# 780-00012-P1_rev2_Sch_M2_Focus_Drive.net
KiCad netlist of a schematic drawn in Altium Designer
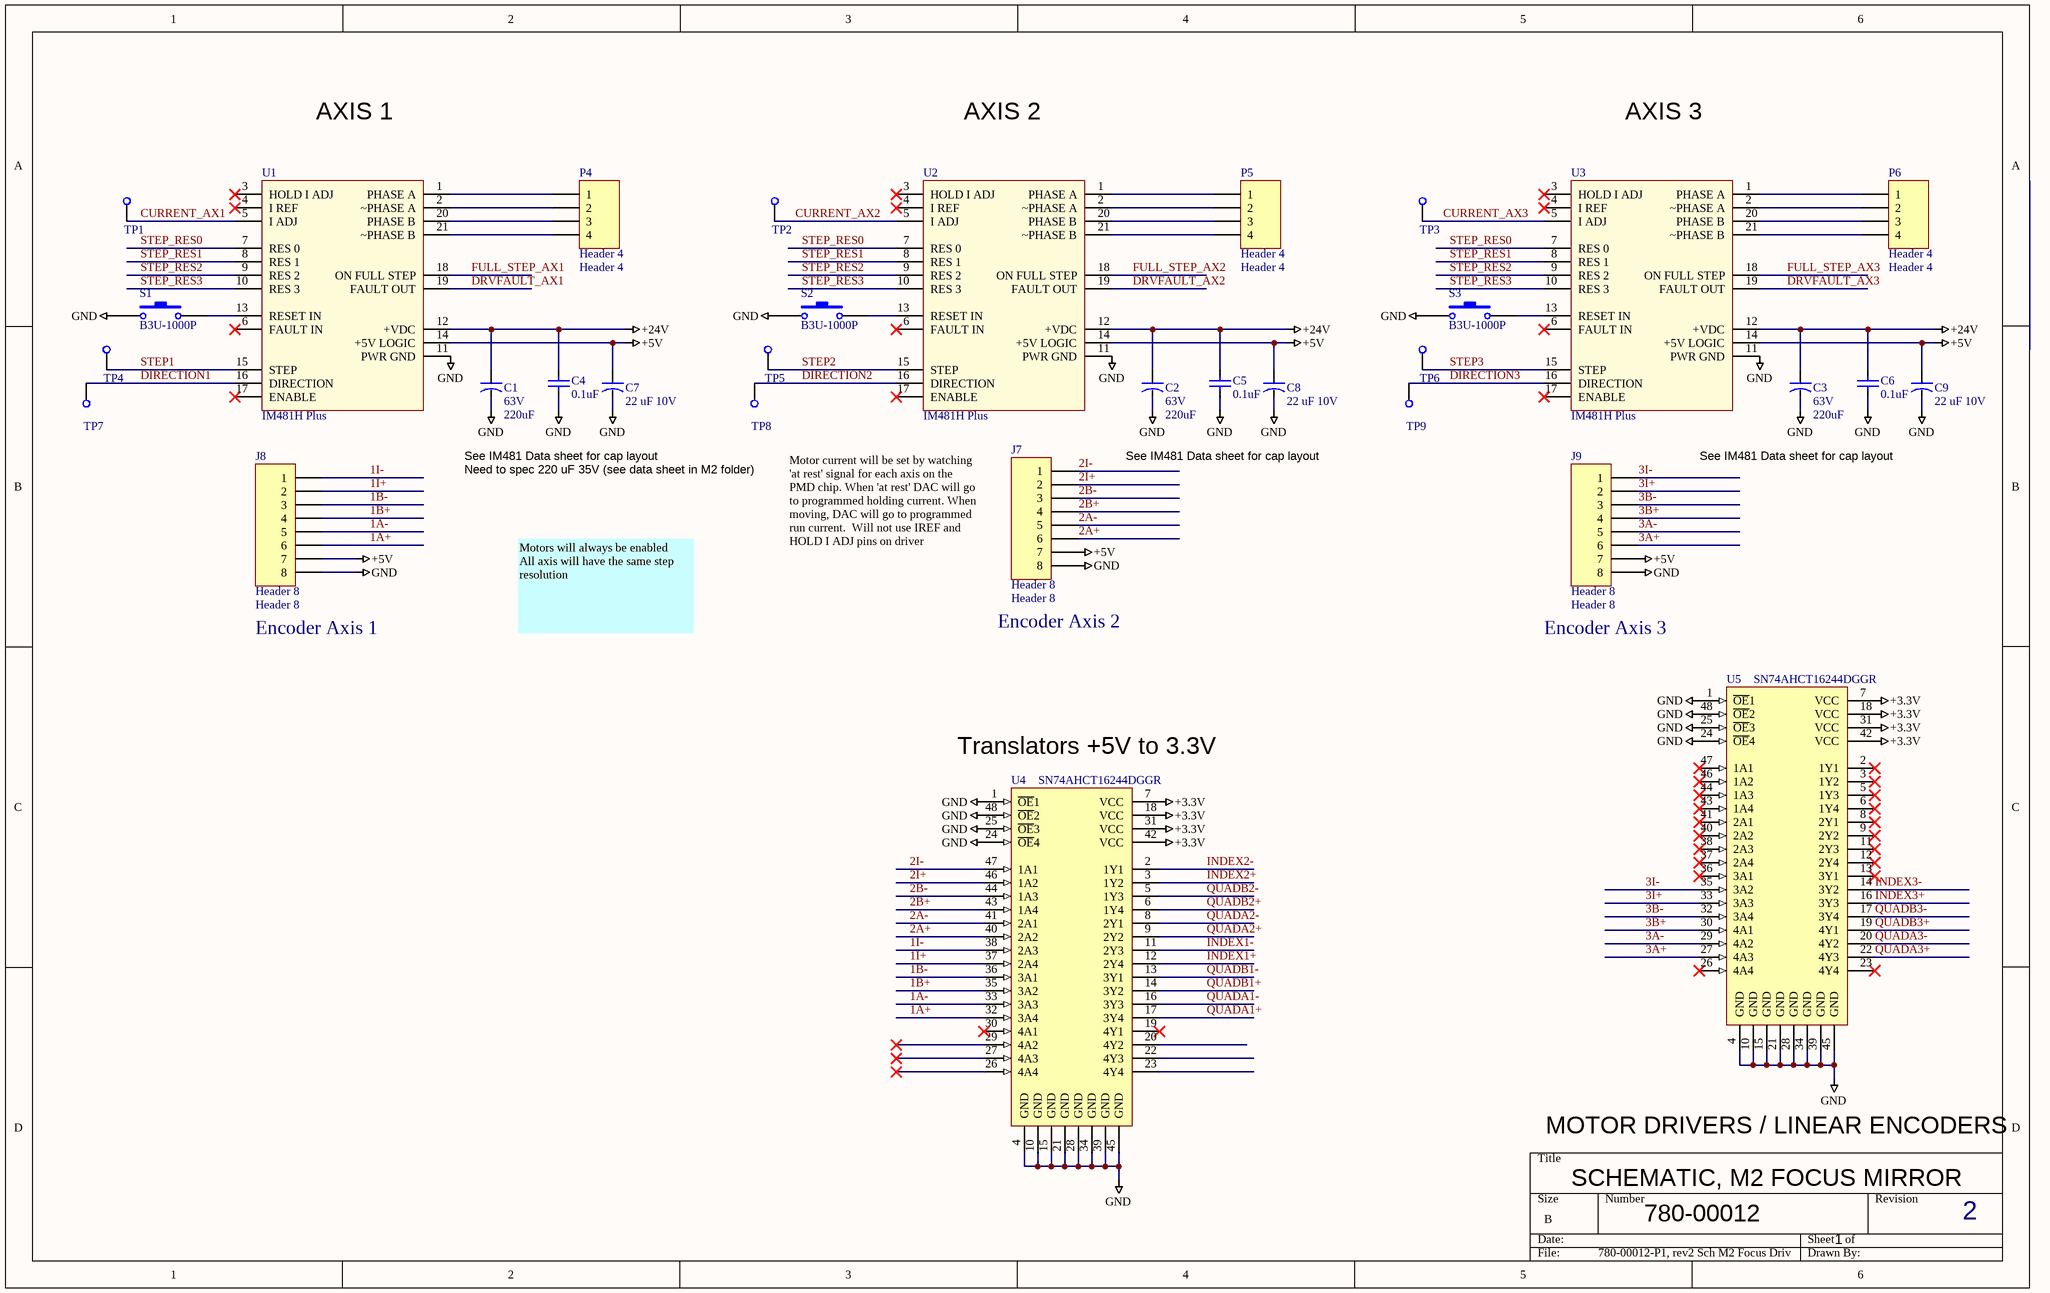
[diagram p0: 780-00012-P1, rev2 Sch M2 Focus Drive.SchDoc]

(export (version "E")
  (design (tool "Eeschema 10.0.6"))
  (components
    (comp (ref "C1")
      (value "63V")
      (footprint "CAP 220uF 63V")
      (description "CAP 220UF 63V ELECT MVH SMD")
      (fields (field (name "MANUFACTURER") "United Chemi-Con") (field (name "ALTIUM_VALUE") "220uF"))
      (libsource (lib "Richs Schematic Components") (part "Cap 220uF, 63V"))
    )
    (comp (ref "C2")
      (value "63V")
      (footprint "CAP 220uF 63V")
      (description "CAP 220UF 63V ELECT MVH SMD")
      (fields (field (name "MANUFACTURER") "United Chemi-Con") (field (name "ALTIUM_VALUE") "220uF"))
      (libsource (lib "Richs Schematic Components") (part "Cap 220uF, 63V"))
    )
    (comp (ref "C3")
      (value "63V")
      (footprint "CAP 220uF 63V")
      (description "CAP 220UF 63V ELECT MVH SMD")
      (fields (field (name "MANUFACTURER") "United Chemi-Con") (field (name "ALTIUM_VALUE") "220uF"))
      (libsource (lib "Richs Schematic Components") (part "Cap 220uF, 63V"))
    )
    (comp (ref "C4")
      (value "0.1uF")
      (footprint "SMD_0805")
      (description "Capacitor")
      (fields (field (name "Comment") "Cap SMD"))
      (libsource (lib "Richs Schematic Components") (part "Cap SMD"))
    )
    (comp (ref "C5")
      (value "0.1uF")
      (footprint "SMD_0805")
      (description "Capacitor")
      (fields (field (name "Comment") "Cap SMD"))
      (libsource (lib "Richs Schematic Components") (part "Cap SMD"))
    )
    (comp (ref "C6")
      (value "0.1uF")
      (footprint "SMD_0805")
      (description "Capacitor")
      (fields (field (name "Comment") "Cap SMD"))
      (libsource (lib "Richs Schematic Components") (part "Cap SMD"))
    )
    (comp (ref "C7")
      (value "22 uF 10V")
      (footprint "SMD_CAP_3216")
      (description "outline 3.2mm x 1.6mm")
      (fields (field (name "MANUFACTURER") "KEMET") (field (name "Comment") "16V"))
      (libsource (lib "Richs Schematic Components") (part "Cap Tant 16V"))
    )
    (comp (ref "C8")
      (value "22 uF 10V")
      (footprint "SMD_CAP_3216")
      (description "outline 3.2mm x 1.6mm")
      (fields (field (name "MANUFACTURER") "KEMET") (field (name "Comment") "16V"))
      (libsource (lib "Richs Schematic Components") (part "Cap Tant 16V"))
    )
    (comp (ref "C9")
      (value "22 uF 10V")
      (footprint "SMD_CAP_3216")
      (description "outline 3.2mm x 1.6mm")
      (fields (field (name "MANUFACTURER") "KEMET") (field (name "Comment") "16V"))
      (libsource (lib "Richs Schematic Components") (part "Cap Tant 16V"))
    )
    (comp (ref "J7")
      (value "Header 8")
      (footprint "HDR1X8 for IDC")
      (description "Header, 8-Pin")
      (fields (field (name "ALTIUM_VALUE") "Header 8"))
      (libsource (lib "Richs Schematic Components") (part "Header 8"))
    )
    (comp (ref "J8")
      (value "Header 8")
      (footprint "HDR1X8 for IDC")
      (description "Header, 8-Pin")
      (fields (field (name "ALTIUM_VALUE") "Header 8"))
      (libsource (lib "Richs Schematic Components") (part "Header 8"))
    )
    (comp (ref "J9")
      (value "Header 8")
      (footprint "HDR1X8 for IDC")
      (description "Header, 8-Pin")
      (fields (field (name "ALTIUM_VALUE") "Header 8"))
      (libsource (lib "Richs Schematic Components") (part "Header 8"))
    )
    (comp (ref "P4")
      (value "Header 4")
      (footprint "HDR1X4 for IDC")
      (description "Header, 4-Pin")
      (fields (field (name "ALTIUM_VALUE") "Header 4"))
      (libsource (lib "Richs Schematic Components") (part "Header 4"))
    )
    (comp (ref "P5")
      (value "Header 4")
      (footprint "HDR1X4 for IDC")
      (description "Header, 4-Pin")
      (fields (field (name "ALTIUM_VALUE") "Header 4"))
      (libsource (lib "Richs Schematic Components") (part "Header 4"))
    )
    (comp (ref "P6")
      (value "Header 4")
      (footprint "HDR1X4 for IDC")
      (description "Header, 4-Pin")
      (fields (field (name "ALTIUM_VALUE") "Header 4"))
      (libsource (lib "Richs Schematic Components") (part "Header 4"))
    )
    (comp (ref "S1")
      (value "B3U-1000P")
      (footprint "B3U-1000P")
      (description "Switch")
      (fields (field (name "MANUFACTURER") "Omron Electronics"))
      (libsource (lib "Miscellaneous Devices") (part "SW-PB"))
    )
    (comp (ref "S2")
      (value "B3U-1000P")
      (footprint "B3U-1000P")
      (description "Switch")
      (fields (field (name "MANUFACTURER") "Omron Electronics"))
      (libsource (lib "Miscellaneous Devices") (part "SW-PB"))
    )
    (comp (ref "S3")
      (value "B3U-1000P")
      (footprint "B3U-1000P")
      (description "Switch")
      (fields (field (name "MANUFACTURER") "Omron Electronics"))
      (libsource (lib "Miscellaneous Devices") (part "SW-PB"))
    )
    (comp (ref "TP1")
      (value "Test Point SMD")
      (footprint "SMD_TEST POINT")
      (description "SMD loop test point")
      (libsource (lib "Richs Schematic Components") (part "Test Point SMD"))
    )
    (comp (ref "TP2")
      (value "Test Point SMD")
      (footprint "SMD_TEST POINT")
      (description "SMD loop test point")
      (libsource (lib "Richs Schematic Components") (part "Test Point SMD"))
    )
    (comp (ref "TP3")
      (value "Test Point SMD")
      (footprint "SMD_TEST POINT")
      (description "SMD loop test point")
      (libsource (lib "Richs Schematic Components") (part "Test Point SMD"))
    )
    (comp (ref "TP4")
      (value "Test Point SMD")
      (footprint "SMD_TEST POINT")
      (description "SMD loop test point")
      (libsource (lib "Richs Schematic Components") (part "Test Point SMD"))
    )
    (comp (ref "TP5")
      (value "Test Point SMD")
      (footprint "SMD_TEST POINT")
      (description "SMD loop test point")
      (libsource (lib "Richs Schematic Components") (part "Test Point SMD"))
    )
    (comp (ref "TP6")
      (value "Test Point SMD")
      (footprint "SMD_TEST POINT")
      (description "SMD loop test point")
      (libsource (lib "Richs Schematic Components") (part "Test Point SMD"))
    )
    (comp (ref "TP7")
      (value "Test Point SMD")
      (footprint "SMD_TEST POINT")
      (description "SMD loop test point")
      (libsource (lib "Richs Schematic Components") (part "Test Point SMD"))
    )
    (comp (ref "TP8")
      (value "Test Point SMD")
      (footprint "SMD_TEST POINT")
      (description "SMD loop test point")
      (libsource (lib "Richs Schematic Components") (part "Test Point SMD"))
    )
    (comp (ref "TP9")
      (value "Test Point SMD")
      (footprint "SMD_TEST POINT")
      (description "SMD loop test point")
      (libsource (lib "Richs Schematic Components") (part "Test Point SMD"))
    )
    (comp (ref "U1")
      (value "IM481H Plus")
      (footprint "IM481H Vertical")
      (description "Hybrid stepper motor driver")
      (libsource (lib "Richs Schematic Components") (part "IM481H Plus"))
    )
    (comp (ref "U2")
      (value "IM481H Plus")
      (footprint "IM481H Vertical")
      (description "Hybrid stepper motor driver")
      (libsource (lib "Richs Schematic Components") (part "IM481H Plus"))
    )
    (comp (ref "U3")
      (value "IM481H Plus")
      (footprint "IM481H Vertical")
      (description "Hybrid stepper motor driver")
      (libsource (lib "Richs Schematic Components") (part "IM481H Plus"))
    )
    (comp (ref "U4")
      (value "SN74AHCT16244DGGR")
      (footprint "DGG048_N")
      (description "16-Bit Buffer/Driver with 3-State Outputs")
      (libsource (lib "TI Logic Buffer Line Driver") (part "SN74AHCT16244DGGR"))
    )
    (comp (ref "U5")
      (value "SN74AHCT16244DGGR")
      (footprint "DGG048_N")
      (description "16-Bit Buffer/Driver with 3-State Outputs")
      (libsource (lib "TI Logic Buffer Line Driver") (part "SN74AHCT16244DGGR"))
    )
  )
  (nets
    (net (code "1") (name "+3.3V") (class "Default")
      (node (ref "U4") (pin "18") (pinfunction "VCC_18") (pintype "power_in"))
      (node (ref "U4") (pin "31") (pinfunction "VCC_31") (pintype "power_in"))
      (node (ref "U4") (pin "42") (pinfunction "VCC_42") (pintype "power_in"))
      (node (ref "U4") (pin "7") (pinfunction "VCC_7") (pintype "power_in"))
      (node (ref "U5") (pin "18") (pinfunction "VCC_18") (pintype "power_in"))
      (node (ref "U5") (pin "31") (pinfunction "VCC_31") (pintype "power_in"))
      (node (ref "U5") (pin "42") (pinfunction "VCC_42") (pintype "power_in"))
      (node (ref "U5") (pin "7") (pinfunction "VCC_7") (pintype "power_in"))
    )
    (net (code "2") (name "+5V") (class "Default")
      (node (ref "C7") (pin "1") (pinfunction "1_1") (pintype "passive"))
      (node (ref "C8") (pin "1") (pinfunction "1_1") (pintype "passive"))
      (node (ref "C9") (pin "1") (pinfunction "1_1") (pintype "passive"))
      (node (ref "J7") (pin "7") (pinfunction "7_7") (pintype "passive"))
      (node (ref "J8") (pin "7") (pinfunction "7_7") (pintype "passive"))
      (node (ref "J9") (pin "7") (pinfunction "7_7") (pintype "passive"))
      (node (ref "U1") (pin "14") (pinfunction "+5V_LOGIC_14") (pintype "passive"))
      (node (ref "U2") (pin "14") (pinfunction "+5V_LOGIC_14") (pintype "passive"))
      (node (ref "U3") (pin "14") (pinfunction "+5V_LOGIC_14") (pintype "passive"))
    )
    (net (code "3") (name "+24V") (class "Default")
      (node (ref "C1") (pin "1") (pinfunction "1_1") (pintype "passive"))
      (node (ref "C2") (pin "1") (pinfunction "1_1") (pintype "passive"))
      (node (ref "C3") (pin "1") (pinfunction "1_1") (pintype "passive"))
      (node (ref "C4") (pin "2") (pinfunction "2_2") (pintype "passive"))
      (node (ref "C5") (pin "2") (pinfunction "2_2") (pintype "passive"))
      (node (ref "C6") (pin "2") (pinfunction "2_2") (pintype "passive"))
      (node (ref "U1") (pin "12") (pinfunction "+VDC_12") (pintype "passive"))
      (node (ref "U2") (pin "12") (pinfunction "+VDC_12") (pintype "passive"))
      (node (ref "U3") (pin "12") (pinfunction "+VDC_12") (pintype "passive"))
    )
    (net (code "4") (name "/1A+") (class "Default")
      (node (ref "J8") (pin "6") (pinfunction "6_6") (pintype "passive"))
      (node (ref "U4") (pin "32") (pinfunction "3A4_32") (pintype "input"))
    )
    (net (code "5") (name "/1A-") (class "Default")
      (node (ref "J8") (pin "5") (pinfunction "5_5") (pintype "passive"))
      (node (ref "U4") (pin "33") (pinfunction "3A3_33") (pintype "input"))
    )
    (net (code "6") (name "/1B+") (class "Default")
      (node (ref "J8") (pin "4") (pinfunction "4_4") (pintype "passive"))
      (node (ref "U4") (pin "35") (pinfunction "3A2_35") (pintype "input"))
    )
    (net (code "7") (name "/1B-") (class "Default")
      (node (ref "J8") (pin "3") (pinfunction "3_3") (pintype "passive"))
      (node (ref "U4") (pin "36") (pinfunction "3A1_36") (pintype "input"))
    )
    (net (code "8") (name "/1I+") (class "Default")
      (node (ref "J8") (pin "2") (pinfunction "2_2") (pintype "passive"))
      (node (ref "U4") (pin "37") (pinfunction "2A4_37") (pintype "input"))
    )
    (net (code "9") (name "/1I-") (class "Default")
      (node (ref "J8") (pin "1") (pinfunction "1_1") (pintype "passive"))
      (node (ref "U4") (pin "38") (pinfunction "2A3_38") (pintype "input"))
    )
    (net (code "10") (name "/2A+") (class "Default")
      (node (ref "J7") (pin "6") (pinfunction "6_6") (pintype "passive"))
      (node (ref "U4") (pin "40") (pinfunction "2A2_40") (pintype "input"))
    )
    (net (code "11") (name "/2A-") (class "Default")
      (node (ref "J7") (pin "5") (pinfunction "5_5") (pintype "passive"))
      (node (ref "U4") (pin "41") (pinfunction "2A1_41") (pintype "input"))
    )
    (net (code "12") (name "/2B+") (class "Default")
      (node (ref "J7") (pin "4") (pinfunction "4_4") (pintype "passive"))
      (node (ref "U4") (pin "43") (pinfunction "1A4_43") (pintype "input"))
    )
    (net (code "13") (name "/2B-") (class "Default")
      (node (ref "J7") (pin "3") (pinfunction "3_3") (pintype "passive"))
      (node (ref "U4") (pin "44") (pinfunction "1A3_44") (pintype "input"))
    )
    (net (code "14") (name "/2I+") (class "Default")
      (node (ref "J7") (pin "2") (pinfunction "2_2") (pintype "passive"))
      (node (ref "U4") (pin "46") (pinfunction "1A2_46") (pintype "input"))
    )
    (net (code "15") (name "/2I-") (class "Default")
      (node (ref "J7") (pin "1") (pinfunction "1_1") (pintype "passive"))
      (node (ref "U4") (pin "47") (pinfunction "1A1_47") (pintype "input"))
    )
    (net (code "16") (name "/3A+") (class "Default")
      (node (ref "J9") (pin "6") (pinfunction "6_6") (pintype "passive"))
      (node (ref "U5") (pin "27") (pinfunction "4A3_27") (pintype "input"))
    )
    (net (code "17") (name "/3A-") (class "Default")
      (node (ref "J9") (pin "5") (pinfunction "5_5") (pintype "passive"))
      (node (ref "U5") (pin "29") (pinfunction "4A2_29") (pintype "input"))
    )
    (net (code "18") (name "/3B+") (class "Default")
      (node (ref "J9") (pin "4") (pinfunction "4_4") (pintype "passive"))
      (node (ref "U5") (pin "30") (pinfunction "4A1_30") (pintype "input"))
    )
    (net (code "19") (name "/3B-") (class "Default")
      (node (ref "J9") (pin "3") (pinfunction "3_3") (pintype "passive"))
      (node (ref "U5") (pin "32") (pinfunction "3A4_32") (pintype "input"))
    )
    (net (code "20") (name "/3I+") (class "Default")
      (node (ref "J9") (pin "2") (pinfunction "2_2") (pintype "passive"))
      (node (ref "U5") (pin "33") (pinfunction "3A3_33") (pintype "input"))
    )
    (net (code "21") (name "/3I-") (class "Default")
      (node (ref "J9") (pin "1") (pinfunction "1_1") (pintype "passive"))
      (node (ref "U5") (pin "35") (pinfunction "3A2_35") (pintype "input"))
    )
    (net (code "22") (name "/CURRENT_AX1") (class "Default")
      (node (ref "TP1") (pin "1") (pinfunction "TP_1") (pintype "passive"))
      (node (ref "U1") (pin "5") (pinfunction "I_ADJ_5") (pintype "passive"))
    )
    (net (code "23") (name "/CURRENT_AX2") (class "Default")
      (node (ref "TP2") (pin "1") (pinfunction "TP_1") (pintype "passive"))
      (node (ref "U2") (pin "5") (pinfunction "I_ADJ_5") (pintype "passive"))
    )
    (net (code "24") (name "/CURRENT_AX3") (class "Default")
      (node (ref "TP3") (pin "1") (pinfunction "TP_1") (pintype "passive"))
      (node (ref "U3") (pin "5") (pinfunction "I_ADJ_5") (pintype "passive"))
    )
    (net (code "25") (name "/DIRECTION1") (class "Default")
      (node (ref "TP7") (pin "1") (pinfunction "TP_1") (pintype "passive"))
      (node (ref "U1") (pin "16") (pinfunction "DIRECTION_16") (pintype "passive"))
    )
    (net (code "26") (name "/DIRECTION2") (class "Default")
      (node (ref "TP8") (pin "1") (pinfunction "TP_1") (pintype "passive"))
      (node (ref "U2") (pin "16") (pinfunction "DIRECTION_16") (pintype "passive"))
    )
    (net (code "27") (name "/DIRECTION3") (class "Default")
      (node (ref "TP9") (pin "1") (pinfunction "TP_1") (pintype "passive"))
      (node (ref "U3") (pin "16") (pinfunction "DIRECTION_16") (pintype "passive"))
    )
    (net (code "28") (name "/DRVFAULT_AX1") (class "Default")
      (node (ref "U1") (pin "19") (pinfunction "FAULT_OUT_19") (pintype "passive"))
    )
    (net (code "29") (name "/DRVFAULT_AX2") (class "Default")
      (node (ref "U2") (pin "19") (pinfunction "FAULT_OUT_19") (pintype "passive"))
    )
    (net (code "30") (name "/DRVFAULT_AX3") (class "Default")
      (node (ref "U3") (pin "19") (pinfunction "FAULT_OUT_19") (pintype "passive"))
    )
    (net (code "31") (name "/FULL_STEP_AX1") (class "Default")
      (node (ref "U1") (pin "18") (pinfunction "ON_FULL_STEP_18") (pintype "passive"))
    )
    (net (code "32") (name "/FULL_STEP_AX2") (class "Default")
      (node (ref "U2") (pin "18") (pinfunction "ON_FULL_STEP_18") (pintype "passive"))
    )
    (net (code "33") (name "/FULL_STEP_AX3") (class "Default")
      (node (ref "U3") (pin "18") (pinfunction "ON_FULL_STEP_18") (pintype "passive"))
    )
    (net (code "34") (name "/INDEX1+") (class "Default")
      (node (ref "U4") (pin "12") (pinfunction "2Y4_12") (pintype "tri_state"))
    )
    (net (code "35") (name "/INDEX1-") (class "Default")
      (node (ref "U4") (pin "11") (pinfunction "2Y3_11") (pintype "tri_state"))
    )
    (net (code "36") (name "/INDEX2+") (class "Default")
      (node (ref "U4") (pin "3") (pinfunction "1Y2_3") (pintype "tri_state"))
    )
    (net (code "37") (name "/INDEX2-") (class "Default")
      (node (ref "U4") (pin "2") (pinfunction "1Y1_2") (pintype "tri_state"))
    )
    (net (code "38") (name "/INDEX3+") (class "Default")
      (node (ref "U5") (pin "16") (pinfunction "3Y3_16") (pintype "tri_state"))
    )
    (net (code "39") (name "/INDEX3-") (class "Default")
      (node (ref "U5") (pin "14") (pinfunction "3Y2_14") (pintype "tri_state"))
    )
    (net (code "40") (name "/QUADA1+") (class "Default")
      (node (ref "U4") (pin "17") (pinfunction "3Y4_17") (pintype "tri_state"))
    )
    (net (code "41") (name "/QUADA1-") (class "Default")
      (node (ref "U4") (pin "16") (pinfunction "3Y3_16") (pintype "tri_state"))
    )
    (net (code "42") (name "/QUADA2+") (class "Default")
      (node (ref "U4") (pin "9") (pinfunction "2Y2_9") (pintype "tri_state"))
    )
    (net (code "43") (name "/QUADA2-") (class "Default")
      (node (ref "U4") (pin "8") (pinfunction "2Y1_8") (pintype "tri_state"))
    )
    (net (code "44") (name "/QUADA3+") (class "Default")
      (node (ref "U5") (pin "22") (pinfunction "4Y3_22") (pintype "tri_state"))
    )
    (net (code "45") (name "/QUADA3-") (class "Default")
      (node (ref "U5") (pin "20") (pinfunction "4Y2_20") (pintype "tri_state"))
    )
    (net (code "46") (name "/QUADB1+") (class "Default")
      (node (ref "U4") (pin "14") (pinfunction "3Y2_14") (pintype "tri_state"))
    )
    (net (code "47") (name "/QUADB1-") (class "Default")
      (node (ref "U4") (pin "13") (pinfunction "3Y1_13") (pintype "tri_state"))
    )
    (net (code "48") (name "/QUADB2+") (class "Default")
      (node (ref "U4") (pin "6") (pinfunction "1Y4_6") (pintype "tri_state"))
    )
    (net (code "49") (name "/QUADB2-") (class "Default")
      (node (ref "U4") (pin "5") (pinfunction "1Y3_5") (pintype "tri_state"))
    )
    (net (code "50") (name "/QUADB3+") (class "Default")
      (node (ref "U5") (pin "19") (pinfunction "4Y1_19") (pintype "tri_state"))
    )
    (net (code "51") (name "/QUADB3-") (class "Default")
      (node (ref "U5") (pin "17") (pinfunction "3Y4_17") (pintype "tri_state"))
    )
    (net (code "52") (name "/STEP1") (class "Default")
      (node (ref "TP4") (pin "1") (pinfunction "TP_1") (pintype "passive"))
      (node (ref "U1") (pin "15") (pinfunction "STEP_15") (pintype "passive"))
    )
    (net (code "53") (name "/STEP2") (class "Default")
      (node (ref "TP5") (pin "1") (pinfunction "TP_1") (pintype "passive"))
      (node (ref "U2") (pin "15") (pinfunction "STEP_15") (pintype "passive"))
    )
    (net (code "54") (name "/STEP3") (class "Default")
      (node (ref "TP6") (pin "1") (pinfunction "TP_1") (pintype "passive"))
      (node (ref "U3") (pin "15") (pinfunction "STEP_15") (pintype "passive"))
    )
    (net (code "55") (name "/STEP_RES0") (class "Default")
      (node (ref "U1") (pin "7") (pinfunction "RES_0_7") (pintype "passive"))
      (node (ref "U2") (pin "7") (pinfunction "RES_0_7") (pintype "passive"))
      (node (ref "U3") (pin "7") (pinfunction "RES_0_7") (pintype "passive"))
    )
    (net (code "56") (name "/STEP_RES1") (class "Default")
      (node (ref "U1") (pin "8") (pinfunction "RES_1_8") (pintype "passive"))
      (node (ref "U2") (pin "8") (pinfunction "RES_1_8") (pintype "passive"))
      (node (ref "U3") (pin "8") (pinfunction "RES_1_8") (pintype "passive"))
    )
    (net (code "57") (name "/STEP_RES2") (class "Default")
      (node (ref "U1") (pin "9") (pinfunction "RES_2_9") (pintype "passive"))
      (node (ref "U2") (pin "9") (pinfunction "RES_2_9") (pintype "passive"))
      (node (ref "U3") (pin "9") (pinfunction "RES_2_9") (pintype "passive"))
    )
    (net (code "58") (name "/STEP_RES3") (class "Default")
      (node (ref "U1") (pin "10") (pinfunction "RES_3_10") (pintype "passive"))
      (node (ref "U2") (pin "10") (pinfunction "RES_3_10") (pintype "passive"))
      (node (ref "U3") (pin "10") (pinfunction "RES_3_10") (pintype "passive"))
    )
    (net (code "59") (name "GND") (class "Default")
      (node (ref "C1") (pin "2") (pinfunction "2_2") (pintype "passive"))
      (node (ref "C2") (pin "2") (pinfunction "2_2") (pintype "passive"))
      (node (ref "C3") (pin "2") (pinfunction "2_2") (pintype "passive"))
      (node (ref "C4") (pin "1") (pinfunction "1_1") (pintype "passive"))
      (node (ref "C5") (pin "1") (pinfunction "1_1") (pintype "passive"))
      (node (ref "C6") (pin "1") (pinfunction "1_1") (pintype "passive"))
      (node (ref "C7") (pin "2") (pinfunction "2_2") (pintype "passive"))
      (node (ref "C8") (pin "2") (pinfunction "2_2") (pintype "passive"))
      (node (ref "C9") (pin "2") (pinfunction "2_2") (pintype "passive"))
      (node (ref "J7") (pin "8") (pinfunction "8_8") (pintype "passive"))
      (node (ref "J8") (pin "8") (pinfunction "8_8") (pintype "passive"))
      (node (ref "J9") (pin "8") (pinfunction "8_8") (pintype "passive"))
      (node (ref "S1") (pin "1") (pinfunction "1_1") (pintype "passive"))
      (node (ref "S2") (pin "1") (pinfunction "1_1") (pintype "passive"))
      (node (ref "S3") (pin "1") (pinfunction "1_1") (pintype "passive"))
      (node (ref "U1") (pin "11") (pinfunction "PWR_GND_11") (pintype "passive"))
      (node (ref "U2") (pin "11") (pinfunction "PWR_GND_11") (pintype "passive"))
      (node (ref "U3") (pin "11") (pinfunction "PWR_GND_11") (pintype "passive"))
      (node (ref "U4") (pin "1") (pinfunction "~{OE}1_1") (pintype "input"))
      (node (ref "U4") (pin "10") (pinfunction "GND_10") (pintype "power_in"))
      (node (ref "U4") (pin "15") (pinfunction "GND_15") (pintype "power_in"))
      (node (ref "U4") (pin "21") (pinfunction "GND_21") (pintype "power_in"))
      (node (ref "U4") (pin "24") (pinfunction "~{OE}4_24") (pintype "input"))
      (node (ref "U4") (pin "25") (pinfunction "~{OE}3_25") (pintype "input"))
      (node (ref "U4") (pin "28") (pinfunction "GND_28") (pintype "power_in"))
      (node (ref "U4") (pin "34") (pinfunction "GND_34") (pintype "power_in"))
      (node (ref "U4") (pin "39") (pinfunction "GND_39") (pintype "power_in"))
      (node (ref "U4") (pin "4") (pinfunction "GND_4") (pintype "power_in"))
      (node (ref "U4") (pin "45") (pinfunction "GND_45") (pintype "power_in"))
      (node (ref "U4") (pin "48") (pinfunction "~{OE}2_48") (pintype "input"))
      (node (ref "U5") (pin "1") (pinfunction "~{OE}1_1") (pintype "input"))
      (node (ref "U5") (pin "10") (pinfunction "GND_10") (pintype "power_in"))
      (node (ref "U5") (pin "15") (pinfunction "GND_15") (pintype "power_in"))
      (node (ref "U5") (pin "21") (pinfunction "GND_21") (pintype "power_in"))
      (node (ref "U5") (pin "24") (pinfunction "~{OE}4_24") (pintype "input"))
      (node (ref "U5") (pin "25") (pinfunction "~{OE}3_25") (pintype "input"))
      (node (ref "U5") (pin "28") (pinfunction "GND_28") (pintype "power_in"))
      (node (ref "U5") (pin "34") (pinfunction "GND_34") (pintype "power_in"))
      (node (ref "U5") (pin "39") (pinfunction "GND_39") (pintype "power_in"))
      (node (ref "U5") (pin "4") (pinfunction "GND_4") (pintype "power_in"))
      (node (ref "U5") (pin "45") (pinfunction "GND_45") (pintype "power_in"))
      (node (ref "U5") (pin "48") (pinfunction "~{OE}2_48") (pintype "input"))
    )
    (net (code "60") (name "Net-(U1-PHASE_A)") (class "Default")
      (node (ref "P4") (pin "1") (pinfunction "1_1") (pintype "passive"))
      (node (ref "U1") (pin "1") (pinfunction "PHASE_A_1") (pintype "passive"))
    )
    (net (code "61") (name "Net-(U1-PHASE_B)") (class "Default")
      (node (ref "P4") (pin "3") (pinfunction "3_3") (pintype "passive"))
      (node (ref "U1") (pin "20") (pinfunction "PHASE_B_20") (pintype "passive"))
    )
    (net (code "62") (name "Net-(U1-RESET_IN)") (class "Default")
      (node (ref "S1") (pin "2") (pinfunction "2_2") (pintype "passive"))
      (node (ref "U1") (pin "13") (pinfunction "RESET_IN_13") (pintype "passive"))
    )
    (net (code "63") (name "Net-(U1-~PHASE_A)") (class "Default")
      (node (ref "P4") (pin "2") (pinfunction "2_2") (pintype "passive"))
      (node (ref "U1") (pin "2") (pinfunction "~PHASE_A_2") (pintype "passive"))
    )
    (net (code "64") (name "Net-(U1-~PHASE_B)") (class "Default")
      (node (ref "P4") (pin "4") (pinfunction "4_4") (pintype "passive"))
      (node (ref "U1") (pin "21") (pinfunction "~PHASE_B_21") (pintype "passive"))
    )
    (net (code "65") (name "Net-(U2-PHASE_A)") (class "Default")
      (node (ref "P5") (pin "1") (pinfunction "1_1") (pintype "passive"))
      (node (ref "U2") (pin "1") (pinfunction "PHASE_A_1") (pintype "passive"))
    )
    (net (code "66") (name "Net-(U2-PHASE_B)") (class "Default")
      (node (ref "P5") (pin "3") (pinfunction "3_3") (pintype "passive"))
      (node (ref "U2") (pin "20") (pinfunction "PHASE_B_20") (pintype "passive"))
    )
    (net (code "67") (name "Net-(U2-RESET_IN)") (class "Default")
      (node (ref "S2") (pin "2") (pinfunction "2_2") (pintype "passive"))
      (node (ref "U2") (pin "13") (pinfunction "RESET_IN_13") (pintype "passive"))
    )
    (net (code "68") (name "Net-(U2-~PHASE_A)") (class "Default")
      (node (ref "P5") (pin "2") (pinfunction "2_2") (pintype "passive"))
      (node (ref "U2") (pin "2") (pinfunction "~PHASE_A_2") (pintype "passive"))
    )
    (net (code "69") (name "Net-(U2-~PHASE_B)") (class "Default")
      (node (ref "P5") (pin "4") (pinfunction "4_4") (pintype "passive"))
      (node (ref "U2") (pin "21") (pinfunction "~PHASE_B_21") (pintype "passive"))
    )
    (net (code "70") (name "Net-(U3-PHASE_A)") (class "Default")
      (node (ref "P6") (pin "1") (pinfunction "1_1") (pintype "passive"))
      (node (ref "U3") (pin "1") (pinfunction "PHASE_A_1") (pintype "passive"))
    )
    (net (code "71") (name "Net-(U3-PHASE_B)") (class "Default")
      (node (ref "P6") (pin "3") (pinfunction "3_3") (pintype "passive"))
      (node (ref "U3") (pin "20") (pinfunction "PHASE_B_20") (pintype "passive"))
    )
    (net (code "72") (name "Net-(U3-RESET_IN)") (class "Default")
      (node (ref "S3") (pin "2") (pinfunction "2_2") (pintype "passive"))
      (node (ref "U3") (pin "13") (pinfunction "RESET_IN_13") (pintype "passive"))
    )
    (net (code "73") (name "Net-(U3-~PHASE_A)") (class "Default")
      (node (ref "P6") (pin "2") (pinfunction "2_2") (pintype "passive"))
      (node (ref "U3") (pin "2") (pinfunction "~PHASE_A_2") (pintype "passive"))
    )
    (net (code "74") (name "Net-(U3-~PHASE_B)") (class "Default")
      (node (ref "P6") (pin "4") (pinfunction "4_4") (pintype "passive"))
      (node (ref "U3") (pin "21") (pinfunction "~PHASE_B_21") (pintype "passive"))
    )
    (net (code "75") (name "unconnected-(U1-ENABLE-Pad17)") (class "Default")
      (node (ref "U1") (pin "17") (pinfunction "ENABLE_17") (pintype "passive+no_connect"))
    )
    (net (code "76") (name "unconnected-(U1-FAULT_IN-Pad6)") (class "Default")
      (node (ref "U1") (pin "6") (pinfunction "FAULT_IN_6") (pintype "passive+no_connect"))
    )
    (net (code "77") (name "unconnected-(U1-HOLD_I_ADJ-Pad3)") (class "Default")
      (node (ref "U1") (pin "3") (pinfunction "HOLD_I_ADJ_3") (pintype "passive+no_connect"))
    )
    (net (code "78") (name "unconnected-(U1-I_REF-Pad4)") (class "Default")
      (node (ref "U1") (pin "4") (pinfunction "I_REF_4") (pintype "passive+no_connect"))
    )
    (net (code "79") (name "unconnected-(U2-ENABLE-Pad17)") (class "Default")
      (node (ref "U2") (pin "17") (pinfunction "ENABLE_17") (pintype "passive+no_connect"))
    )
    (net (code "80") (name "unconnected-(U2-FAULT_IN-Pad6)") (class "Default")
      (node (ref "U2") (pin "6") (pinfunction "FAULT_IN_6") (pintype "passive+no_connect"))
    )
    (net (code "81") (name "unconnected-(U2-HOLD_I_ADJ-Pad3)") (class "Default")
      (node (ref "U2") (pin "3") (pinfunction "HOLD_I_ADJ_3") (pintype "passive+no_connect"))
    )
    (net (code "82") (name "unconnected-(U2-I_REF-Pad4)") (class "Default")
      (node (ref "U2") (pin "4") (pinfunction "I_REF_4") (pintype "passive+no_connect"))
    )
    (net (code "83") (name "unconnected-(U3-ENABLE-Pad17)") (class "Default")
      (node (ref "U3") (pin "17") (pinfunction "ENABLE_17") (pintype "passive+no_connect"))
    )
    (net (code "84") (name "unconnected-(U3-FAULT_IN-Pad6)") (class "Default")
      (node (ref "U3") (pin "6") (pinfunction "FAULT_IN_6") (pintype "passive+no_connect"))
    )
    (net (code "85") (name "unconnected-(U3-HOLD_I_ADJ-Pad3)") (class "Default")
      (node (ref "U3") (pin "3") (pinfunction "HOLD_I_ADJ_3") (pintype "passive+no_connect"))
    )
    (net (code "86") (name "unconnected-(U3-I_REF-Pad4)") (class "Default")
      (node (ref "U3") (pin "4") (pinfunction "I_REF_4") (pintype "passive+no_connect"))
    )
    (net (code "87") (name "unconnected-(U4-4A1-Pad30)") (class "Default")
      (node (ref "U4") (pin "30") (pinfunction "4A1_30") (pintype "input+no_connect"))
    )
    (net (code "88") (name "unconnected-(U4-4A2-Pad29)") (class "Default")
      (node (ref "U4") (pin "29") (pinfunction "4A2_29") (pintype "input+no_connect"))
    )
    (net (code "89") (name "unconnected-(U4-4A3-Pad27)") (class "Default")
      (node (ref "U4") (pin "27") (pinfunction "4A3_27") (pintype "input+no_connect"))
    )
    (net (code "90") (name "unconnected-(U4-4A4-Pad26)") (class "Default")
      (node (ref "U4") (pin "26") (pinfunction "4A4_26") (pintype "input+no_connect"))
    )
    (net (code "91") (name "unconnected-(U4-4Y1-Pad19)") (class "Default")
      (node (ref "U4") (pin "19") (pinfunction "4Y1_19") (pintype "tri_state+no_connect"))
    )
    (net (code "92") (name "unconnected-(U4-4Y2-Pad20)") (class "Default")
      (node (ref "U4") (pin "20") (pinfunction "4Y2_20") (pintype "tri_state"))
    )
    (net (code "93") (name "unconnected-(U4-4Y3-Pad22)") (class "Default")
      (node (ref "U4") (pin "22") (pinfunction "4Y3_22") (pintype "tri_state"))
    )
    (net (code "94") (name "unconnected-(U4-4Y4-Pad23)") (class "Default")
      (node (ref "U4") (pin "23") (pinfunction "4Y4_23") (pintype "tri_state"))
    )
    (net (code "95") (name "unconnected-(U5-1A1-Pad47)") (class "Default")
      (node (ref "U5") (pin "47") (pinfunction "1A1_47") (pintype "input+no_connect"))
    )
    (net (code "96") (name "unconnected-(U5-1A2-Pad46)") (class "Default")
      (node (ref "U5") (pin "46") (pinfunction "1A2_46") (pintype "input+no_connect"))
    )
    (net (code "97") (name "unconnected-(U5-1A3-Pad44)") (class "Default")
      (node (ref "U5") (pin "44") (pinfunction "1A3_44") (pintype "input+no_connect"))
    )
    (net (code "98") (name "unconnected-(U5-1A4-Pad43)") (class "Default")
      (node (ref "U5") (pin "43") (pinfunction "1A4_43") (pintype "input+no_connect"))
    )
    (net (code "99") (name "unconnected-(U5-1Y1-Pad2)") (class "Default")
      (node (ref "U5") (pin "2") (pinfunction "1Y1_2") (pintype "tri_state+no_connect"))
    )
    (net (code "100") (name "unconnected-(U5-1Y2-Pad3)") (class "Default")
      (node (ref "U5") (pin "3") (pinfunction "1Y2_3") (pintype "tri_state+no_connect"))
    )
    (net (code "101") (name "unconnected-(U5-1Y3-Pad5)") (class "Default")
      (node (ref "U5") (pin "5") (pinfunction "1Y3_5") (pintype "tri_state+no_connect"))
    )
    (net (code "102") (name "unconnected-(U5-1Y4-Pad6)") (class "Default")
      (node (ref "U5") (pin "6") (pinfunction "1Y4_6") (pintype "tri_state+no_connect"))
    )
    (net (code "103") (name "unconnected-(U5-2A1-Pad41)") (class "Default")
      (node (ref "U5") (pin "41") (pinfunction "2A1_41") (pintype "input+no_connect"))
    )
    (net (code "104") (name "unconnected-(U5-2A2-Pad40)") (class "Default")
      (node (ref "U5") (pin "40") (pinfunction "2A2_40") (pintype "input+no_connect"))
    )
    (net (code "105") (name "unconnected-(U5-2A3-Pad38)") (class "Default")
      (node (ref "U5") (pin "38") (pinfunction "2A3_38") (pintype "input+no_connect"))
    )
    (net (code "106") (name "unconnected-(U5-2A4-Pad37)") (class "Default")
      (node (ref "U5") (pin "37") (pinfunction "2A4_37") (pintype "input+no_connect"))
    )
    (net (code "107") (name "unconnected-(U5-2Y1-Pad8)") (class "Default")
      (node (ref "U5") (pin "8") (pinfunction "2Y1_8") (pintype "tri_state+no_connect"))
    )
    (net (code "108") (name "unconnected-(U5-2Y2-Pad9)") (class "Default")
      (node (ref "U5") (pin "9") (pinfunction "2Y2_9") (pintype "tri_state+no_connect"))
    )
    (net (code "109") (name "unconnected-(U5-2Y3-Pad11)") (class "Default")
      (node (ref "U5") (pin "11") (pinfunction "2Y3_11") (pintype "tri_state+no_connect"))
    )
    (net (code "110") (name "unconnected-(U5-2Y4-Pad12)") (class "Default")
      (node (ref "U5") (pin "12") (pinfunction "2Y4_12") (pintype "tri_state+no_connect"))
    )
    (net (code "111") (name "unconnected-(U5-3A1-Pad36)") (class "Default")
      (node (ref "U5") (pin "36") (pinfunction "3A1_36") (pintype "input+no_connect"))
    )
    (net (code "112") (name "unconnected-(U5-3Y1-Pad13)") (class "Default")
      (node (ref "U5") (pin "13") (pinfunction "3Y1_13") (pintype "tri_state+no_connect"))
    )
    (net (code "113") (name "unconnected-(U5-4A4-Pad26)") (class "Default")
      (node (ref "U5") (pin "26") (pinfunction "4A4_26") (pintype "input+no_connect"))
    )
    (net (code "114") (name "unconnected-(U5-4Y4-Pad23)") (class "Default")
      (node (ref "U5") (pin "23") (pinfunction "4Y4_23") (pintype "tri_state+no_connect"))
    )
  )
)
